# YAW_POWER.net
KiCad netlist of a schematic drawn in Altium Designer
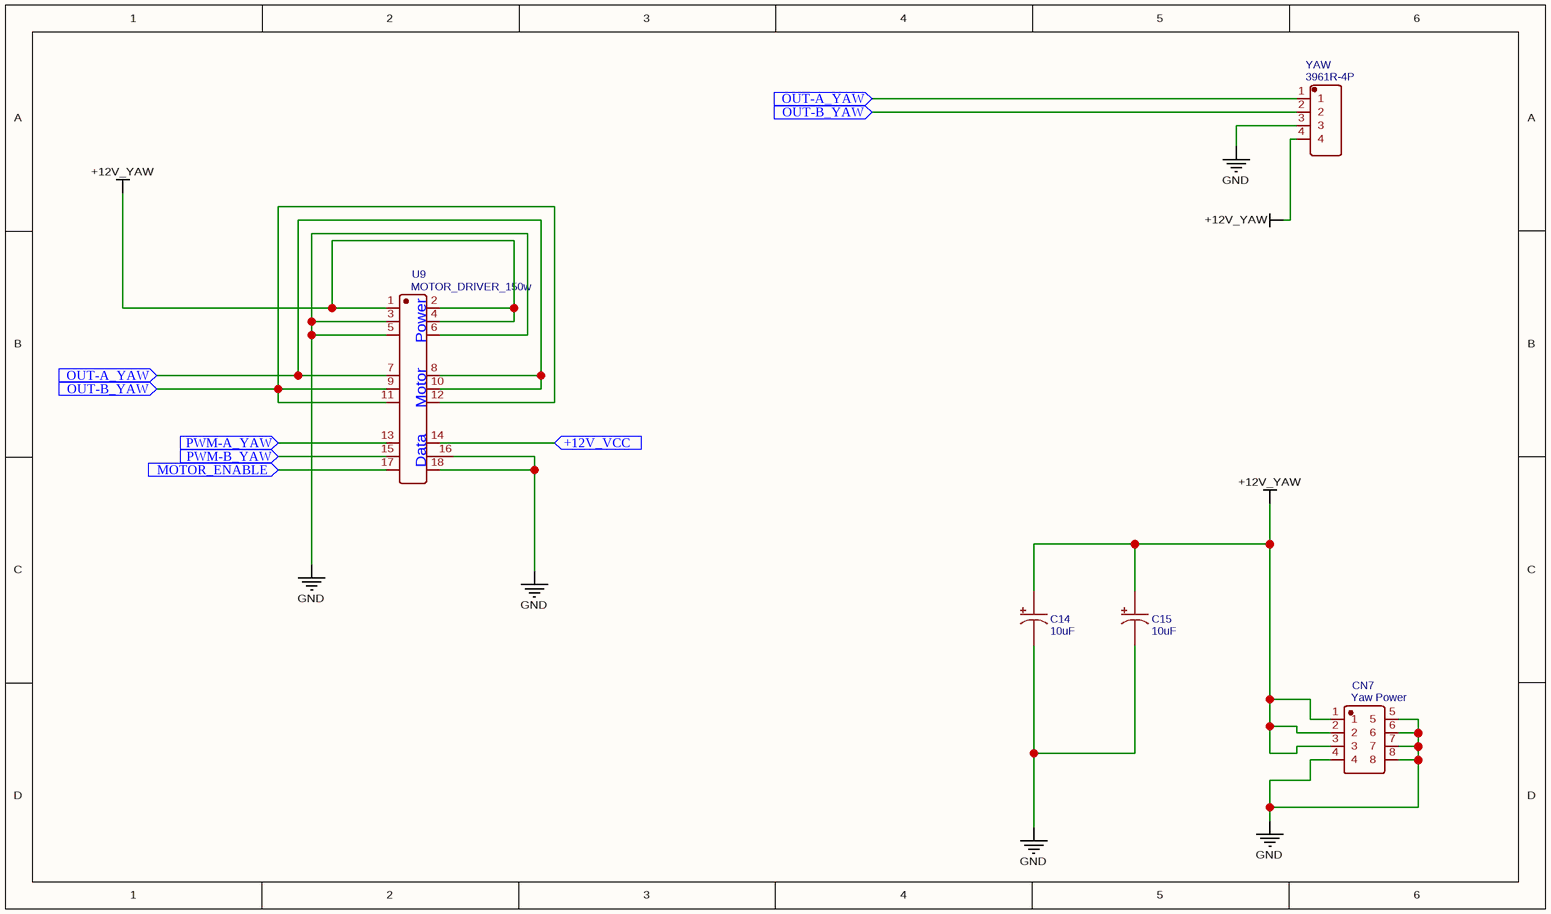
[diagram p0: YAW_POWER.schdoc]

(export (version "E")
  (design (tool "Eeschema 10.0.6"))
  (components
    (comp (ref "C14")
      (value "10uF")
      (fields
        (field (name "BOM_SUPPLIER PART") "C213486")
        (field (name "BOM_MANUFACTURER PART") "VT1E100M0405")
        (field (name "CONTRIBUTOR") "LCSC")
      )
      (libsource (lib "altium-import") (part "root_1_10uF_"))
    )
    (comp (ref "C15")
      (value "10uF")
      (fields
        (field (name "BOM_SUPPLIER PART") "C213486")
        (field (name "BOM_MANUFACTURER PART") "VT1E100M0405")
        (field (name "CONTRIBUTOR") "LCSC")
      )
      (libsource (lib "altium-import") (part "root_1_10uF_"))
    )
    (comp (ref "CN7")
      (value "Yaw Power")
      (fields
        (field (name "BOM_SUPPLIER PART") "C519240")
        (field (name "BOM_MANUFACTURER PART") "X9357WV-2*04-N2SN")
        (field (name "CONTRIBUTOR") "LCSC")
      )
      (libsource (lib "altium-import") (part "root_0_Yaw Power_"))
    )
    (comp (ref "U9")
      (value "MOTOR_DRIVER_150w")
      (fields (field (name "CONTRIBUTOR") "digitalman"))
      (libsource (lib "altium-import") (part "root_3_MOTOR_DRIVER_150w_"))
    )
    (comp (ref "YAW")
      (value "3961R-4P")
      (fields (field (name "BOM_SUPPLIER PART") "C138427") (field (name "CONTRIBUTOR") "LCSC"))
      (libsource (lib "altium-import") (part "root_0_3961R-4P_"))
    )
  )
  (nets
    (net (code "1") (name "+12V_YAW") (class "Default")
      (node (ref "C14") (pin "1") (pinfunction "1_1") (pintype "passive"))
      (node (ref "C15") (pin "1") (pinfunction "1_1") (pintype "passive"))
      (node (ref "CN7") (pin "1") (pinfunction "1_1") (pintype "passive"))
      (node (ref "CN7") (pin "2") (pinfunction "2_2") (pintype "passive"))
      (node (ref "CN7") (pin "3") (pinfunction "3_3") (pintype "passive"))
      (node (ref "U9") (pin "1") (pinfunction "+12V_YAW_1") (pintype "passive"))
      (node (ref "U9") (pin "2") (pinfunction "+12V_YAW_2") (pintype "passive"))
      (node (ref "U9") (pin "4") (pinfunction "+12V_YAW_4") (pintype "passive"))
      (node (ref "YAW") (pin "4") (pinfunction "4_4") (pintype "passive"))
    )
    (net (code "2") (name "/+12V_VCC") (class "Default")
      (node (ref "U9") (pin "14") (pinfunction "+12V_VCC_14") (pintype "passive"))
    )
    (net (code "3") (name "/MOTOR_ENABLE") (class "Default")
      (node (ref "U9") (pin "17") (pinfunction "MOTOR_ENABLE_17") (pintype "passive"))
    )
    (net (code "4") (name "/OUT-A_YAW") (class "Default")
      (node (ref "U9") (pin "10") (pinfunction "OUT-A_YAW_10") (pintype "passive"))
      (node (ref "U9") (pin "7") (pinfunction "OUT-A_YAW_7") (pintype "passive"))
      (node (ref "U9") (pin "8") (pinfunction "OUT-A_YAW_8") (pintype "passive"))
      (node (ref "YAW") (pin "1") (pinfunction "1_1") (pintype "passive"))
    )
    (net (code "5") (name "/OUT-B_YAW") (class "Default")
      (node (ref "U9") (pin "11") (pinfunction "OUT-B_YAW_11") (pintype "passive"))
      (node (ref "U9") (pin "12") (pinfunction "OUT-B_YAW_12") (pintype "passive"))
      (node (ref "U9") (pin "9") (pinfunction "OUT-B_YAW_9") (pintype "passive"))
      (node (ref "YAW") (pin "2") (pinfunction "2_2") (pintype "passive"))
    )
    (net (code "6") (name "/PWM-A_YAW") (class "Default")
      (node (ref "U9") (pin "13") (pinfunction "PWM-A_YAW_13") (pintype "passive"))
    )
    (net (code "7") (name "/PWM-B_YAW") (class "Default")
      (node (ref "U9") (pin "15") (pinfunction "PWM-B_YAW_15") (pintype "passive"))
    )
    (net (code "8") (name "GND") (class "Default")
      (node (ref "C14") (pin "2") (pinfunction "2_2") (pintype "passive"))
      (node (ref "C15") (pin "2") (pinfunction "2_2") (pintype "passive"))
      (node (ref "CN7") (pin "4") (pinfunction "4_4") (pintype "passive"))
      (node (ref "CN7") (pin "5") (pinfunction "5_5") (pintype "passive"))
      (node (ref "CN7") (pin "6") (pinfunction "6_6") (pintype "passive"))
      (node (ref "CN7") (pin "7") (pinfunction "7_7") (pintype "passive"))
      (node (ref "CN7") (pin "8") (pinfunction "8_8") (pintype "passive"))
      (node (ref "U9") (pin "16") (pinfunction "GND_16") (pintype "passive"))
      (node (ref "U9") (pin "18") (pinfunction "GND_18") (pintype "passive"))
      (node (ref "U9") (pin "3") (pinfunction "GND_3") (pintype "passive"))
      (node (ref "U9") (pin "5") (pinfunction "GND_5") (pintype "passive"))
      (node (ref "U9") (pin "6") (pinfunction "GND_6") (pintype "passive"))
      (node (ref "YAW") (pin "3") (pinfunction "3_3") (pintype "passive"))
    )
  )
)
